# main.net
KiCad netlist of a schematic drawn in EAGLE
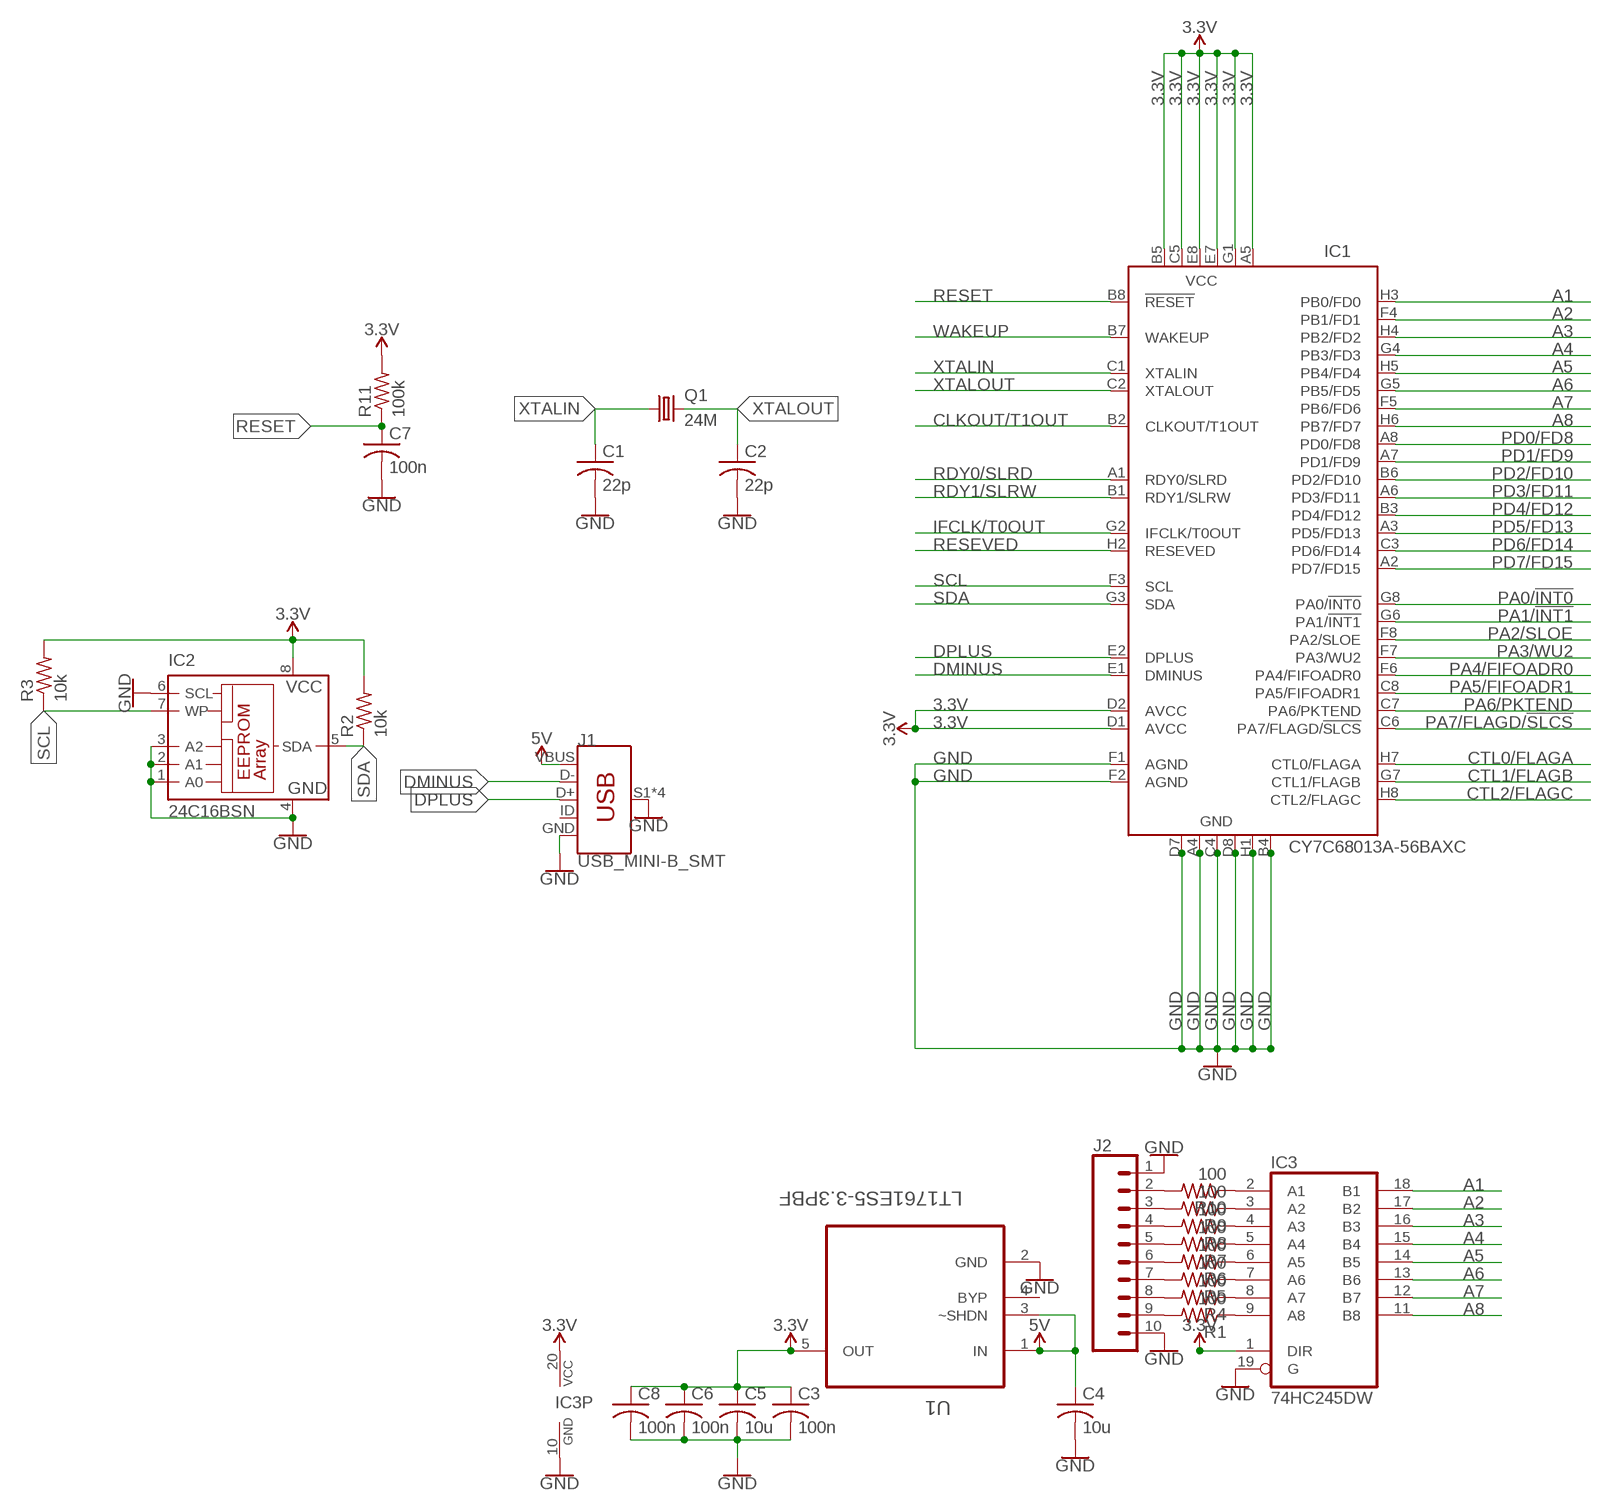
[diagram p0: schematic, sheet 1]

(export (version "E")
  (design (tool "Eeschema 10.0.6"))
  (components
    (comp (ref "C1")
      (value "22p")
      (footprint "eagle-import:C0201")
      (libsource (lib "eagle-import") (part "C-USC0201"))
    )
    (comp (ref "C2")
      (value "22p")
      (footprint "eagle-import:C0201")
      (libsource (lib "eagle-import") (part "C-USC0201"))
    )
    (comp (ref "C3")
      (value "100n")
      (footprint "eagle-import:C0201")
      (libsource (lib "eagle-import") (part "C-USC0201"))
    )
    (comp (ref "C4")
      (value "10u")
      (footprint "eagle-import:C0603K")
      (libsource (lib "eagle-import") (part "C-USC0603K"))
    )
    (comp (ref "C5")
      (value "10u")
      (footprint "eagle-import:C0603K")
      (libsource (lib "eagle-import") (part "C-USC0603K"))
    )
    (comp (ref "C6")
      (value "100n")
      (footprint "eagle-import:C0201")
      (libsource (lib "eagle-import") (part "C-USC0201"))
    )
    (comp (ref "C7")
      (value "100n")
      (footprint "eagle-import:C0201")
      (libsource (lib "eagle-import") (part "C-USC0201"))
    )
    (comp (ref "C8")
      (value "100n")
      (footprint "eagle-import:C0201")
      (libsource (lib "eagle-import") (part "C-USC0201"))
    )
    (comp (ref "IC1")
      (value "CY7C68013A-56BAXC")
      (footprint "eagle-import:VFBGA56")
      (fields (field (name "MF") "CYPRESS SEMICONDUCTOR CORPORAT") (field (name "SPICEPREFIX") "X"))
      (libsource (lib "eagle-import") (part "CY7C6801A-56BAXC3"))
    )
    (comp (ref "IC2")
      (value "24C16BSN")
      (footprint "eagle-import:SO-08")
      (fields (field (name "MPN") "AT24C16BN-SH-B"))
      (libsource (lib "eagle-import") (part "24SNC16B"))
    )
    (comp (ref "IC3")
      (value "74HC245DW")
      (footprint "eagle-import:SO20W")
      (libsource (lib "eagle-import") (part "74245DWHC"))
    )
    (comp (ref "J1")
      (value "USB_MINI-B_SMT")
      (footprint "eagle-import:USB-MINIB")
      (libsource (lib "eagle-import") (part "USB_MINI-B_SMT"))
    )
    (comp (ref "J2")
      (value "CONN_10SMD")
      (footprint "eagle-import:1X10_SMD")
      (libsource (lib "eagle-import") (part "CONN_10SMD"))
    )
    (comp (ref "Q1")
      (value "24M")
      (footprint "eagle-import:CSM-7X-DU")
      (libsource (lib "eagle-import") (part "CSM-7X-DU"))
    )
    (comp (ref "R1")
      (value "100")
      (footprint "eagle-import:R0201")
      (libsource (lib "eagle-import") (part "R-US_R0201"))
    )
    (comp (ref "R2")
      (value "10k")
      (footprint "eagle-import:R0201")
      (libsource (lib "eagle-import") (part "R-US_R0201"))
    )
    (comp (ref "R3")
      (value "10k")
      (footprint "eagle-import:R0201")
      (libsource (lib "eagle-import") (part "R-US_R0201"))
    )
    (comp (ref "R4")
      (value "100")
      (footprint "eagle-import:R0201")
      (libsource (lib "eagle-import") (part "R-US_R0201"))
    )
    (comp (ref "R5")
      (value "100")
      (footprint "eagle-import:R0201")
      (libsource (lib "eagle-import") (part "R-US_R0201"))
    )
    (comp (ref "R6")
      (value "100")
      (footprint "eagle-import:R0201")
      (libsource (lib "eagle-import") (part "R-US_R0201"))
    )
    (comp (ref "R7")
      (value "100")
      (footprint "eagle-import:R0201")
      (libsource (lib "eagle-import") (part "R-US_R0201"))
    )
    (comp (ref "R8")
      (value "100")
      (footprint "eagle-import:R0201")
      (libsource (lib "eagle-import") (part "R-US_R0201"))
    )
    (comp (ref "R9")
      (value "100")
      (footprint "eagle-import:R0201")
      (libsource (lib "eagle-import") (part "R-US_R0201"))
    )
    (comp (ref "R10")
      (value "100")
      (footprint "eagle-import:R0201")
      (libsource (lib "eagle-import") (part "R-US_R0201"))
    )
    (comp (ref "R11")
      (value "100k")
      (footprint "eagle-import:R0201")
      (libsource (lib "eagle-import") (part "R-US_R0201"))
    )
    (comp (ref "U1")
      (value "LT1761ES5-3.3PBF")
      (footprint "eagle-import:SOT95P280X100-5N")
      (fields (field (name "MPN") "LT1761ES5-3.3#PBF"))
      (libsource (lib "eagle-import") (part "LT1761ES5-3.3PBF"))
    )
  )
  (nets
    (net (code "1") (name "/A1") (class "Default")
      (node (ref "IC1") (pin "H3") (pinfunction "PB0/FD0_H3") (pintype "bidirectional"))
      (node (ref "IC3") (pin "18") (pinfunction "B1_18") (pintype "bidirectional"))
    )
    (net (code "2") (name "/A2") (class "Default")
      (node (ref "IC1") (pin "F4") (pinfunction "PB1/FD1_F4") (pintype "bidirectional"))
      (node (ref "IC3") (pin "17") (pinfunction "B2_17") (pintype "bidirectional"))
    )
    (net (code "3") (name "/A3") (class "Default")
      (node (ref "IC1") (pin "H4") (pinfunction "PB2/FD2_H4") (pintype "bidirectional"))
      (node (ref "IC3") (pin "16") (pinfunction "B3_16") (pintype "bidirectional"))
    )
    (net (code "4") (name "/A4") (class "Default")
      (node (ref "IC1") (pin "G4") (pinfunction "PB3/FD3_G4") (pintype "bidirectional"))
      (node (ref "IC3") (pin "15") (pinfunction "B4_15") (pintype "bidirectional"))
    )
    (net (code "5") (name "/A5") (class "Default")
      (node (ref "IC1") (pin "H5") (pinfunction "PB4/FD4_H5") (pintype "bidirectional"))
      (node (ref "IC3") (pin "14") (pinfunction "B5_14") (pintype "bidirectional"))
    )
    (net (code "6") (name "/A6") (class "Default")
      (node (ref "IC1") (pin "G5") (pinfunction "PB5/FD5_G5") (pintype "bidirectional"))
      (node (ref "IC3") (pin "13") (pinfunction "B6_13") (pintype "bidirectional"))
    )
    (net (code "7") (name "/A7") (class "Default")
      (node (ref "IC1") (pin "F5") (pinfunction "PB6/FD6_F5") (pintype "bidirectional"))
      (node (ref "IC3") (pin "12") (pinfunction "B7_12") (pintype "bidirectional"))
    )
    (net (code "8") (name "/A8") (class "Default")
      (node (ref "IC1") (pin "H6") (pinfunction "PB7/FD7_H6") (pintype "bidirectional"))
      (node (ref "IC3") (pin "11") (pinfunction "B8_11") (pintype "bidirectional"))
    )
    (net (code "9") (name "/CLKOUT{slash}T1OUT") (class "Default")
      (node (ref "IC1") (pin "B2") (pinfunction "CLKOUT/T1OUT_B2") (pintype "input"))
    )
    (net (code "10") (name "/CTL0{slash}FLAGA") (class "Default")
      (node (ref "IC1") (pin "H7") (pinfunction "CTL0/FLAGA_H7") (pintype "output"))
    )
    (net (code "11") (name "/CTL1{slash}FLAGB") (class "Default")
      (node (ref "IC1") (pin "G7") (pinfunction "CTL1/FLAGB_G7") (pintype "output"))
    )
    (net (code "12") (name "/CTL2{slash}FLAGC") (class "Default")
      (node (ref "IC1") (pin "H8") (pinfunction "CTL2/FLAGC_H8") (pintype "output"))
    )
    (net (code "13") (name "/IFCLK{slash}T0OUT") (class "Default")
      (node (ref "IC1") (pin "G2") (pinfunction "IFCLK/T0OUT_G2") (pintype "bidirectional"))
    )
    (net (code "14") (name "/PA0{slash}~{INT0}") (class "Default")
      (node (ref "IC1") (pin "G8") (pinfunction "PA0/~{INT0}_G8") (pintype "bidirectional"))
    )
    (net (code "15") (name "/PA1{slash}~{INT1}") (class "Default")
      (node (ref "IC1") (pin "G6") (pinfunction "PA1/~{INT1}_G6") (pintype "bidirectional"))
    )
    (net (code "16") (name "/PA2{slash}SLOE") (class "Default")
      (node (ref "IC1") (pin "F8") (pinfunction "PA2/SLOE_F8") (pintype "bidirectional"))
    )
    (net (code "17") (name "/PA3{slash}WU2") (class "Default")
      (node (ref "IC1") (pin "F7") (pinfunction "PA3/WU2_F7") (pintype "bidirectional"))
    )
    (net (code "18") (name "/PA4{slash}FIFOADR0") (class "Default")
      (node (ref "IC1") (pin "F6") (pinfunction "PA4/FIFOADR0_F6") (pintype "bidirectional"))
    )
    (net (code "19") (name "/PA5{slash}FIFOADR1") (class "Default")
      (node (ref "IC1") (pin "C8") (pinfunction "PA5/FIFOADR1_C8") (pintype "bidirectional"))
    )
    (net (code "20") (name "/PA6{slash}PKTEND") (class "Default")
      (node (ref "IC1") (pin "C7") (pinfunction "PA6/PKTEND_C7") (pintype "bidirectional"))
    )
    (net (code "21") (name "/PA7{slash}FLAGD{slash}~{SLCS}") (class "Default")
      (node (ref "IC1") (pin "C6") (pinfunction "PA7/FLAGD/~{SLCS}_C6") (pintype "bidirectional"))
    )
    (net (code "22") (name "/PD0{slash}FD8") (class "Default")
      (node (ref "IC1") (pin "A8") (pinfunction "PD0/FD8_A8") (pintype "bidirectional"))
    )
    (net (code "23") (name "/PD1{slash}FD9") (class "Default")
      (node (ref "IC1") (pin "A7") (pinfunction "PD1/FD9_A7") (pintype "bidirectional"))
    )
    (net (code "24") (name "/PD2{slash}FD10") (class "Default")
      (node (ref "IC1") (pin "B6") (pinfunction "PD2/FD10_B6") (pintype "bidirectional"))
    )
    (net (code "25") (name "/PD3{slash}FD11") (class "Default")
      (node (ref "IC1") (pin "A6") (pinfunction "PD3/FD11_A6") (pintype "bidirectional"))
    )
    (net (code "26") (name "/PD4{slash}FD12") (class "Default")
      (node (ref "IC1") (pin "B3") (pinfunction "PD4/FD12_B3") (pintype "bidirectional"))
    )
    (net (code "27") (name "/PD5{slash}FD13") (class "Default")
      (node (ref "IC1") (pin "A3") (pinfunction "PD5/FD13_A3") (pintype "bidirectional"))
    )
    (net (code "28") (name "/PD6{slash}FD14") (class "Default")
      (node (ref "IC1") (pin "C3") (pinfunction "PD6/FD14_C3") (pintype "bidirectional"))
    )
    (net (code "29") (name "/PD7{slash}FD15") (class "Default")
      (node (ref "IC1") (pin "A2") (pinfunction "PD7/FD15_A2") (pintype "bidirectional"))
    )
    (net (code "30") (name "/RDY0{slash}SLRD") (class "Default")
      (node (ref "IC1") (pin "A1") (pinfunction "RDY0/SLRD_A1") (pintype "input"))
    )
    (net (code "31") (name "/RDY1{slash}SLRW") (class "Default")
      (node (ref "IC1") (pin "B1") (pinfunction "RDY1/SLRW_B1") (pintype "input"))
    )
    (net (code "32") (name "/RESEVED") (class "Default")
      (node (ref "IC1") (pin "H2") (pinfunction "RESEVED_H2") (pintype "input"))
    )
    (net (code "33") (name "/WAKEUP") (class "Default")
      (node (ref "IC1") (pin "B7") (pinfunction "WAKEUP_B7") (pintype "input"))
    )
    (net (code "34") (name "3.3V") (class "Default")
      (node (ref "C3") (pin "1") (pinfunction "1_1") (pintype "passive"))
      (node (ref "C5") (pin "1") (pinfunction "1_1") (pintype "passive"))
      (node (ref "C6") (pin "1") (pinfunction "1_1") (pintype "passive"))
      (node (ref "C8") (pin "1") (pinfunction "1_1") (pintype "passive"))
      (node (ref "IC1") (pin "A5") (pinfunction "VCC_A5") (pintype "input"))
      (node (ref "IC1") (pin "B5") (pinfunction "VCC_B5") (pintype "input"))
      (node (ref "IC1") (pin "C5") (pinfunction "VCC_C5") (pintype "input"))
      (node (ref "IC1") (pin "D1") (pinfunction "AVCC_D1") (pintype "input"))
      (node (ref "IC1") (pin "D2") (pinfunction "AVCC_D2") (pintype "input"))
      (node (ref "IC1") (pin "E7") (pinfunction "VCC_E7") (pintype "input"))
      (node (ref "IC1") (pin "E8") (pinfunction "VCC_E8") (pintype "input"))
      (node (ref "IC1") (pin "G1") (pinfunction "VCC_G1") (pintype "input"))
      (node (ref "IC2") (pin "8") (pinfunction "VCC_8") (pintype "power_in"))
      (node (ref "IC3") (pin "1") (pinfunction "DIR_1") (pintype "input"))
      (node (ref "IC3") (pin "20") (pinfunction "VCC_20") (pintype "power_in"))
      (node (ref "R11") (pin "2") (pinfunction "2_2") (pintype "passive"))
      (node (ref "R2") (pin "2") (pinfunction "2_2") (pintype "passive"))
      (node (ref "R3") (pin "2") (pinfunction "2_2") (pintype "passive"))
      (node (ref "U1") (pin "5") (pinfunction "OUT_5") (pintype "output"))
    )
    (net (code "35") (name "5V") (class "Default")
      (node (ref "C4") (pin "1") (pinfunction "1_1") (pintype "passive"))
      (node (ref "J1") (pin "VBUS") (pinfunction "VBUS_VBUS") (pintype "power_in"))
      (node (ref "U1") (pin "1") (pinfunction "IN_1") (pintype "input"))
      (node (ref "U1") (pin "3") (pinfunction "~{SHDN}_3") (pintype "input"))
    )
    (net (code "36") (name "DMINUS") (class "Default")
      (node (ref "IC1") (pin "E1") (pinfunction "DMINUS_E1") (pintype "bidirectional"))
      (node (ref "J1") (pin "D-") (pinfunction "D-_D-") (pintype "bidirectional"))
    )
    (net (code "37") (name "DPLUS") (class "Default")
      (node (ref "IC1") (pin "E2") (pinfunction "DPLUS_E2") (pintype "bidirectional"))
      (node (ref "J1") (pin "D+") (pinfunction "D+_D+") (pintype "bidirectional"))
    )
    (net (code "38") (name "GND") (class "Default")
      (node (ref "C1") (pin "2") (pinfunction "2_2") (pintype "passive"))
      (node (ref "C2") (pin "2") (pinfunction "2_2") (pintype "passive"))
      (node (ref "C3") (pin "2") (pinfunction "2_2") (pintype "passive"))
      (node (ref "C4") (pin "2") (pinfunction "2_2") (pintype "passive"))
      (node (ref "C5") (pin "2") (pinfunction "2_2") (pintype "passive"))
      (node (ref "C6") (pin "2") (pinfunction "2_2") (pintype "passive"))
      (node (ref "C7") (pin "2") (pinfunction "2_2") (pintype "passive"))
      (node (ref "C8") (pin "2") (pinfunction "2_2") (pintype "passive"))
      (node (ref "IC1") (pin "A4") (pinfunction "GND_A4") (pintype "input"))
      (node (ref "IC1") (pin "B4") (pinfunction "GND_B4") (pintype "input"))
      (node (ref "IC1") (pin "C4") (pinfunction "GND_C4") (pintype "input"))
      (node (ref "IC1") (pin "D7") (pinfunction "GND_D7") (pintype "input"))
      (node (ref "IC1") (pin "D8") (pinfunction "GND_D8") (pintype "input"))
      (node (ref "IC1") (pin "F1") (pinfunction "AGND_F1") (pintype "input"))
      (node (ref "IC1") (pin "F2") (pinfunction "AGND_F2") (pintype "input"))
      (node (ref "IC1") (pin "H1") (pinfunction "GND_H1") (pintype "input"))
      (node (ref "IC2") (pin "1") (pinfunction "A0_1") (pintype "input"))
      (node (ref "IC2") (pin "2") (pinfunction "A1_2") (pintype "input"))
      (node (ref "IC2") (pin "3") (pinfunction "A2_3") (pintype "input"))
      (node (ref "IC2") (pin "4") (pinfunction "GND_4") (pintype "power_in"))
      (node (ref "IC2") (pin "6") (pinfunction "SCL_6") (pintype "input"))
      (node (ref "IC3") (pin "10") (pinfunction "GND_10") (pintype "power_in"))
      (node (ref "IC3") (pin "19") (pinfunction "G_19") (pintype "input"))
      (node (ref "J1") (pin "GND") (pinfunction "GND_GND") (pintype "power_in"))
      (node (ref "J1") (pin "S1") (pinfunction "SHIELD_S1") (pintype "bidirectional"))
      (node (ref "J1") (pin "S2") (pinfunction "SHIELD_S2") (pintype "bidirectional"))
      (node (ref "J1") (pin "S3") (pinfunction "SHIELD_S3") (pintype "bidirectional"))
      (node (ref "J1") (pin "S4") (pinfunction "SHIELD_S4") (pintype "bidirectional"))
      (node (ref "J2") (pin "1") (pinfunction "1_1") (pintype "passive"))
      (node (ref "J2") (pin "10") (pinfunction "10_10") (pintype "passive"))
      (node (ref "U1") (pin "2") (pinfunction "GND_2") (pintype "passive"))
    )
    (net (code "39") (name "Net-(IC3A-A1)") (class "Default")
      (node (ref "IC3") (pin "2") (pinfunction "A1_2") (pintype "bidirectional"))
      (node (ref "R10") (pin "1") (pinfunction "1_1") (pintype "passive"))
    )
    (net (code "40") (name "Net-(IC3A-A2)") (class "Default")
      (node (ref "IC3") (pin "3") (pinfunction "A2_3") (pintype "bidirectional"))
      (node (ref "R9") (pin "1") (pinfunction "1_1") (pintype "passive"))
    )
    (net (code "41") (name "Net-(IC3A-A3)") (class "Default")
      (node (ref "IC3") (pin "4") (pinfunction "A3_4") (pintype "bidirectional"))
      (node (ref "R8") (pin "1") (pinfunction "1_1") (pintype "passive"))
    )
    (net (code "42") (name "Net-(IC3A-A4)") (class "Default")
      (node (ref "IC3") (pin "5") (pinfunction "A4_5") (pintype "bidirectional"))
      (node (ref "R7") (pin "1") (pinfunction "1_1") (pintype "passive"))
    )
    (net (code "43") (name "Net-(IC3A-A5)") (class "Default")
      (node (ref "IC3") (pin "6") (pinfunction "A5_6") (pintype "bidirectional"))
      (node (ref "R6") (pin "1") (pinfunction "1_1") (pintype "passive"))
    )
    (net (code "44") (name "Net-(IC3A-A6)") (class "Default")
      (node (ref "IC3") (pin "7") (pinfunction "A6_7") (pintype "bidirectional"))
      (node (ref "R5") (pin "1") (pinfunction "1_1") (pintype "passive"))
    )
    (net (code "45") (name "Net-(IC3A-A7)") (class "Default")
      (node (ref "IC3") (pin "8") (pinfunction "A7_8") (pintype "bidirectional"))
      (node (ref "R4") (pin "1") (pinfunction "1_1") (pintype "passive"))
    )
    (net (code "46") (name "Net-(IC3A-A8)") (class "Default")
      (node (ref "IC3") (pin "9") (pinfunction "A8_9") (pintype "bidirectional"))
      (node (ref "R1") (pin "1") (pinfunction "1_1") (pintype "passive"))
    )
    (net (code "47") (name "Net-(J2-Pad2)") (class "Default")
      (node (ref "J2") (pin "2") (pinfunction "2_2") (pintype "passive"))
      (node (ref "R10") (pin "2") (pinfunction "2_2") (pintype "passive"))
    )
    (net (code "48") (name "Net-(J2-Pad3)") (class "Default")
      (node (ref "J2") (pin "3") (pinfunction "3_3") (pintype "passive"))
      (node (ref "R9") (pin "2") (pinfunction "2_2") (pintype "passive"))
    )
    (net (code "49") (name "Net-(J2-Pad4)") (class "Default")
      (node (ref "J2") (pin "4") (pinfunction "4_4") (pintype "passive"))
      (node (ref "R8") (pin "2") (pinfunction "2_2") (pintype "passive"))
    )
    (net (code "50") (name "Net-(J2-Pad5)") (class "Default")
      (node (ref "J2") (pin "5") (pinfunction "5_5") (pintype "passive"))
      (node (ref "R7") (pin "2") (pinfunction "2_2") (pintype "passive"))
    )
    (net (code "51") (name "Net-(J2-Pad6)") (class "Default")
      (node (ref "J2") (pin "6") (pinfunction "6_6") (pintype "passive"))
      (node (ref "R6") (pin "2") (pinfunction "2_2") (pintype "passive"))
    )
    (net (code "52") (name "Net-(J2-Pad7)") (class "Default")
      (node (ref "J2") (pin "7") (pinfunction "7_7") (pintype "passive"))
      (node (ref "R5") (pin "2") (pinfunction "2_2") (pintype "passive"))
    )
    (net (code "53") (name "Net-(J2-Pad8)") (class "Default")
      (node (ref "J2") (pin "8") (pinfunction "8_8") (pintype "passive"))
      (node (ref "R4") (pin "2") (pinfunction "2_2") (pintype "passive"))
    )
    (net (code "54") (name "Net-(J2-Pad9)") (class "Default")
      (node (ref "J2") (pin "9") (pinfunction "9_9") (pintype "passive"))
      (node (ref "R1") (pin "2") (pinfunction "2_2") (pintype "passive"))
    )
    (net (code "55") (name "RESET") (class "Default")
      (node (ref "C7") (pin "1") (pinfunction "1_1") (pintype "passive"))
      (node (ref "IC1") (pin "B8") (pinfunction "~{RESET}_B8") (pintype "input"))
      (node (ref "R11") (pin "1") (pinfunction "1_1") (pintype "passive"))
    )
    (net (code "56") (name "SCL") (class "Default")
      (node (ref "IC1") (pin "F3") (pinfunction "SCL_F3") (pintype "output"))
      (node (ref "IC2") (pin "7") (pinfunction "WP_7") (pintype "input"))
      (node (ref "R3") (pin "1") (pinfunction "1_1") (pintype "passive"))
    )
    (net (code "57") (name "SDA") (class "Default")
      (node (ref "IC1") (pin "G3") (pinfunction "SDA_G3") (pintype "bidirectional"))
      (node (ref "IC2") (pin "5") (pinfunction "SDA_5") (pintype "bidirectional"))
      (node (ref "R2") (pin "1") (pinfunction "1_1") (pintype "passive"))
    )
    (net (code "58") (name "XTALIN") (class "Default")
      (node (ref "C1") (pin "1") (pinfunction "1_1") (pintype "passive"))
      (node (ref "IC1") (pin "C1") (pinfunction "XTALIN_C1") (pintype "input"))
      (node (ref "Q1") (pin "1") (pinfunction "1_1") (pintype "passive"))
    )
    (net (code "59") (name "XTALOUT") (class "Default")
      (node (ref "C2") (pin "1") (pinfunction "1_1") (pintype "passive"))
      (node (ref "IC1") (pin "C2") (pinfunction "XTALOUT_C2") (pintype "input"))
      (node (ref "Q1") (pin "2") (pinfunction "2_2") (pintype "passive"))
    )
    (net (code "60") (name "unconnected-(J1-PadID)") (class "Default")
      (node (ref "J1") (pin "ID") (pinfunction "ID_ID") (pintype "bidirectional"))
    )
    (net (code "61") (name "unconnected-(U1-BYP-Pad4)") (class "Default")
      (node (ref "U1") (pin "4") (pinfunction "BYP_4") (pintype "passive"))
    )
  )
)
